# SchematicV0.net
KiCad netlist of a schematic drawn in EAGLE
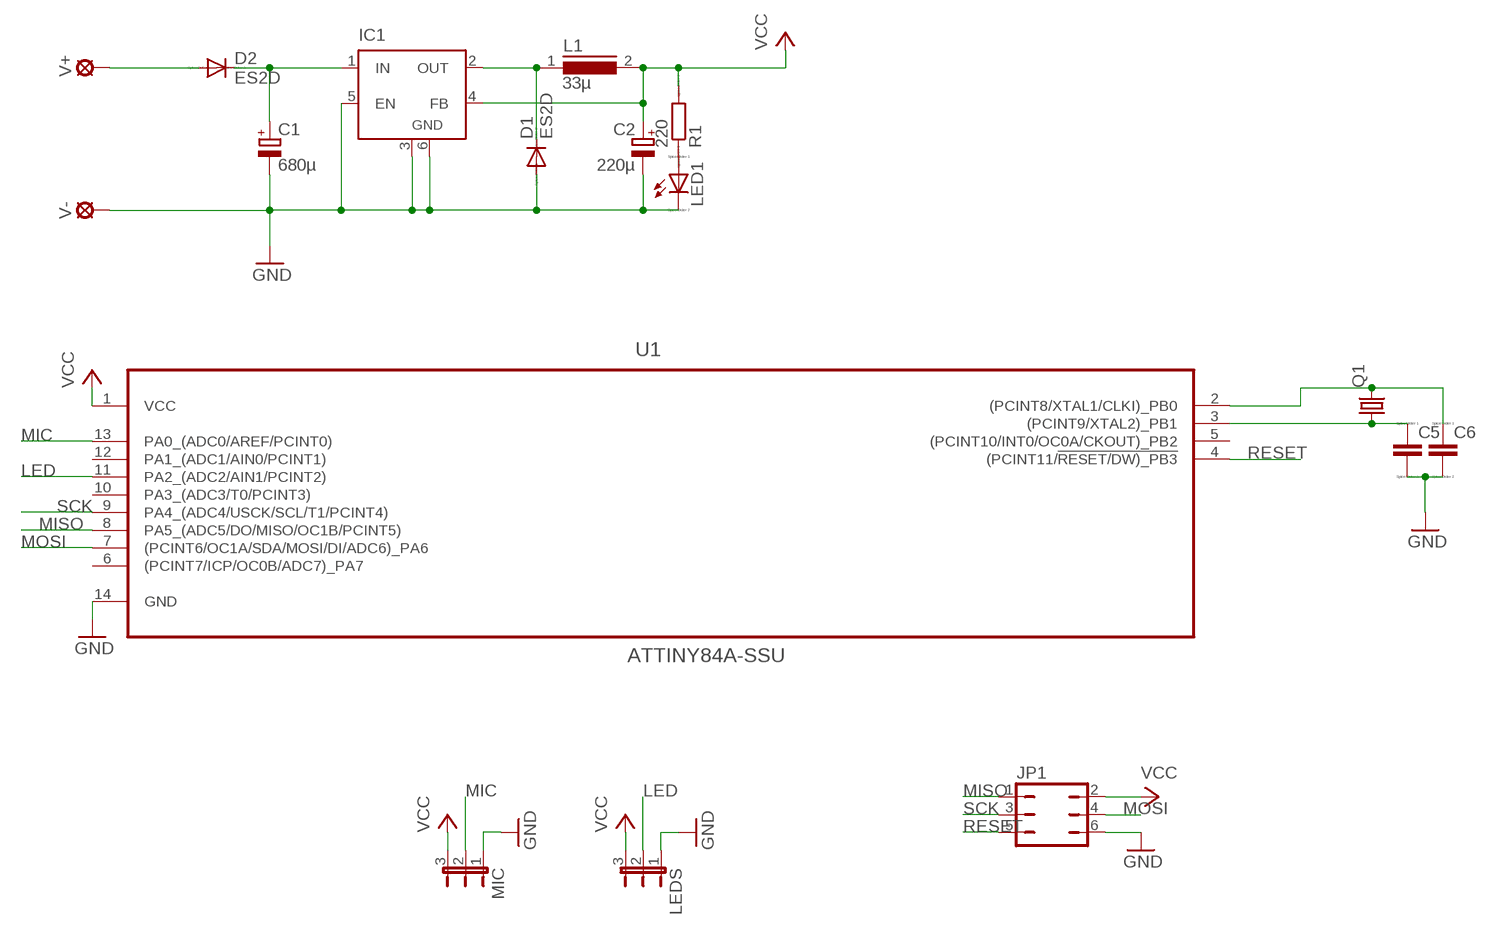
[diagram p0: schematic, sheet 1]

(export (version "E")
  (design (tool "Eeschema 10.0.6"))
  (components
    (comp (ref "C1")
      (value "680µ")
      (footprint "eagle-import:140CLH-1010")
      (libsource (lib "eagle-import") (part "CPOL-EU140CLH-1010"))
    )
    (comp (ref "C2")
      (value "220µ")
      (footprint "eagle-import:140CLH-1010")
      (libsource (lib "eagle-import") (part "CPOL-EU140CLH-1010"))
    )
    (comp (ref "C5")
      (value "CC1005")
      (footprint "eagle-import:C1005")
      (libsource (lib "eagle-import") (part "CC1005"))
    )
    (comp (ref "C6")
      (value "CC1005")
      (footprint "eagle-import:C1005")
      (libsource (lib "eagle-import") (part "CC1005"))
    )
    (comp (ref "D1")
      (value "ES2D")
      (footprint "eagle-import:SMB")
      (libsource (lib "eagle-import") (part "ES2D"))
    )
    (comp (ref "D2")
      (value "ES2D")
      (footprint "eagle-import:SMB")
      (libsource (lib "eagle-import") (part "ES2D"))
    )
    (comp (ref "IC1")
      (value "LM2596S")
      (footprint "eagle-import:TO263-5")
      (libsource (lib "eagle-import") (part "LM2596S"))
    )
    (comp (ref "JP1")
      (value "JP3Q")
      (footprint "eagle-import:JP3Q")
      (libsource (lib "eagle-import") (part "JP3Q"))
    )
    (comp (ref "L1")
      (value "33µ")
      (footprint "eagle-import:DR125")
      (libsource (lib "eagle-import") (part "DR125"))
    )
    (comp (ref "LED1")
      (value "LED_E")
      (footprint "eagle-import:LED_1206")
      (libsource (lib "eagle-import") (part "LED_E"))
    )
    (comp (ref "LEDS")
      (value "JP2E")
      (footprint "eagle-import:JP2")
      (libsource (lib "eagle-import") (part "JP2E"))
    )
    (comp (ref "MIC")
      (value "JP2E")
      (footprint "eagle-import:JP2")
      (libsource (lib "eagle-import") (part "JP2E"))
    )
    (comp (ref "Q1")
      (value "CRYSTALHC49S")
      (footprint "eagle-import:HC49_S")
      (libsource (lib "eagle-import") (part "CRYSTALHC49S"))
    )
    (comp (ref "R1")
      (value "220")
      (footprint "eagle-import:R0805")
      (libsource (lib "eagle-import") (part "R"))
    )
    (comp (ref "U1")
      (value "ATTINY84A-SSU")
      (footprint "eagle-import:SOIC127P600X175-14N")
      (libsource (lib "eagle-import") (part "ATTINY84A-SSU"))
    )
    (comp (ref "V+")
      (value "SE14")
      (footprint "eagle-import:SE14")
      (libsource (lib "eagle-import") (part "SE14"))
    )
    (comp (ref "V-")
      (value "SE14")
      (footprint "eagle-import:SE14")
      (libsource (lib "eagle-import") (part "SE14"))
    )
  )
  (nets
    (net (code "1") (name "/LED") (class "Default")
      (node (ref "LEDS") (pin "2") (pinfunction "2_2") (pintype "passive"))
      (node (ref "U1") (pin "11") (pinfunction "PA2_(ADC2/AIN1/PCINT2)_11") (pintype "bidirectional"))
    )
    (net (code "2") (name "/MIC") (class "Default")
      (node (ref "MIC") (pin "2") (pinfunction "2_2") (pintype "passive"))
      (node (ref "U1") (pin "13") (pinfunction "PA0_(ADC0/AREF/PCINT0)_13") (pintype "bidirectional"))
    )
    (net (code "3") (name "/MISO") (class "Default")
      (node (ref "JP1") (pin "1") (pinfunction "1_1") (pintype "passive"))
      (node (ref "U1") (pin "8") (pinfunction "PA5_(ADC5/DO/MISO/OC1B/PCINT5)_8") (pintype "bidirectional"))
    )
    (net (code "4") (name "/MOSI") (class "Default")
      (node (ref "JP1") (pin "4") (pinfunction "4_4") (pintype "passive"))
      (node (ref "U1") (pin "7") (pinfunction "(PCINT6/OC1A/SDA/MOSI/DI/ADC6)_PA6_7") (pintype "bidirectional"))
    )
    (net (code "5") (name "/RESET") (class "Default")
      (node (ref "JP1") (pin "5") (pinfunction "5_5") (pintype "passive"))
      (node (ref "U1") (pin "4") (pinfunction "(PCINT11/~{RESET/DW})_PB3_4") (pintype "bidirectional"))
    )
    (net (code "6") (name "/SCK") (class "Default")
      (node (ref "JP1") (pin "3") (pinfunction "3_3") (pintype "passive"))
      (node (ref "U1") (pin "9") (pinfunction "PA4_(ADC4/USCK/SCL/T1/PCINT4)_9") (pintype "bidirectional"))
    )
    (net (code "7") (name "GND") (class "Default")
      (node (ref "C1") (pin "-") (pinfunction "-_-") (pintype "passive"))
      (node (ref "C2") (pin "-") (pinfunction "-_-") (pintype "passive"))
      (node (ref "C5") (pin "2") (pinfunction "2_2") (pintype "passive"))
      (node (ref "C6") (pin "2") (pinfunction "2_2") (pintype "passive"))
      (node (ref "D1") (pin "A") (pinfunction "A_A") (pintype "passive"))
      (node (ref "IC1") (pin "3") (pinfunction "GND_3") (pintype "power_in"))
      (node (ref "IC1") (pin "5") (pinfunction "EN_5") (pintype "input"))
      (node (ref "IC1") (pin "6") (pinfunction "GND_6") (pintype "power_in"))
      (node (ref "JP1") (pin "6") (pinfunction "6_6") (pintype "passive"))
      (node (ref "LED1") (pin "C") (pinfunction "C_C") (pintype "passive"))
      (node (ref "LEDS") (pin "1") (pinfunction "1_1") (pintype "passive"))
      (node (ref "MIC") (pin "1") (pinfunction "1_1") (pintype "passive"))
      (node (ref "U1") (pin "14") (pinfunction "GND_14") (pintype "passive"))
      (node (ref "V-") (pin "MP") (pinfunction "MP_MP") (pintype "passive"))
    )
    (net (code "8") (name "Net-(D2-PadA)") (class "Default")
      (node (ref "D2") (pin "A") (pinfunction "A_A") (pintype "passive"))
      (node (ref "V+") (pin "MP") (pinfunction "MP_MP") (pintype "passive"))
    )
    (net (code "9") (name "Net-(IC1-IN)") (class "Default")
      (node (ref "C1") (pin "+") (pinfunction "+_+") (pintype "passive"))
      (node (ref "D2") (pin "C") (pinfunction "C_C") (pintype "passive"))
      (node (ref "IC1") (pin "1") (pinfunction "IN_1") (pintype "input"))
    )
    (net (code "10") (name "Net-(IC1-OUT)") (class "Default")
      (node (ref "D1") (pin "C") (pinfunction "C_C") (pintype "passive"))
      (node (ref "IC1") (pin "2") (pinfunction "OUT_2") (pintype "output"))
      (node (ref "L1") (pin "1") (pinfunction "1_1") (pintype "passive"))
    )
    (net (code "11") (name "Net-(LED1-PadA)") (class "Default")
      (node (ref "LED1") (pin "A") (pinfunction "A_A") (pintype "passive"))
      (node (ref "R1") (pin "1") (pinfunction "1_1") (pintype "passive"))
    )
    (net (code "12") (name "Net-(U1-(PCINT8{slash}XTAL1{slash}CLKI)_PB0)") (class "Default")
      (node (ref "C6") (pin "1") (pinfunction "1_1") (pintype "passive"))
      (node (ref "Q1") (pin "2") (pinfunction "2_2") (pintype "passive"))
      (node (ref "U1") (pin "2") (pinfunction "(PCINT8/XTAL1/CLKI)_PB0_2") (pintype "bidirectional"))
    )
    (net (code "13") (name "Net-(U1-(PCINT9{slash}XTAL2)_PB1)") (class "Default")
      (node (ref "C5") (pin "1") (pinfunction "1_1") (pintype "passive"))
      (node (ref "Q1") (pin "1") (pinfunction "1_1") (pintype "passive"))
      (node (ref "U1") (pin "3") (pinfunction "(PCINT9/XTAL2)_PB1_3") (pintype "bidirectional"))
    )
    (net (code "14") (name "VCC") (class "Default")
      (node (ref "C2") (pin "+") (pinfunction "+_+") (pintype "passive"))
      (node (ref "IC1") (pin "4") (pinfunction "FB_4") (pintype "input"))
      (node (ref "JP1") (pin "2") (pinfunction "2_2") (pintype "passive"))
      (node (ref "L1") (pin "2") (pinfunction "2_2") (pintype "passive"))
      (node (ref "LEDS") (pin "3") (pinfunction "3_3") (pintype "passive"))
      (node (ref "MIC") (pin "3") (pinfunction "3_3") (pintype "passive"))
      (node (ref "R1") (pin "2") (pinfunction "2_2") (pintype "passive"))
      (node (ref "U1") (pin "1") (pinfunction "VCC_1") (pintype "power_in"))
    )
    (net (code "15") (name "unconnected-(U1-(PCINT7{slash}ICP{slash}OC0B{slash}ADC7)_PA7-Pad6)") (class "Default")
      (node (ref "U1") (pin "6") (pinfunction "(PCINT7/ICP/OC0B/ADC7)_PA7_6") (pintype "bidirectional"))
    )
    (net (code "16") (name "unconnected-(U1-(PCINT10{slash}INT0{slash}OC0A{slash}CKOUT)_PB2-Pad5)") (class "Default")
      (node (ref "U1") (pin "5") (pinfunction "(PCINT10/INT0/OC0A/CKOUT)_PB2_5") (pintype "bidirectional"))
    )
    (net (code "17") (name "unconnected-(U1-PA1_(ADC1{slash}AIN0{slash}PCINT1)-Pad12)") (class "Default")
      (node (ref "U1") (pin "12") (pinfunction "PA1_(ADC1/AIN0/PCINT1)_12") (pintype "bidirectional"))
    )
    (net (code "18") (name "unconnected-(U1-PA3_(ADC3{slash}T0{slash}PCINT3)-Pad10)") (class "Default")
      (node (ref "U1") (pin "10") (pinfunction "PA3_(ADC3/T0/PCINT3)_10") (pintype "bidirectional"))
    )
  )
)
